# uC.net
KiCad netlist of a schematic drawn in Altium Designer
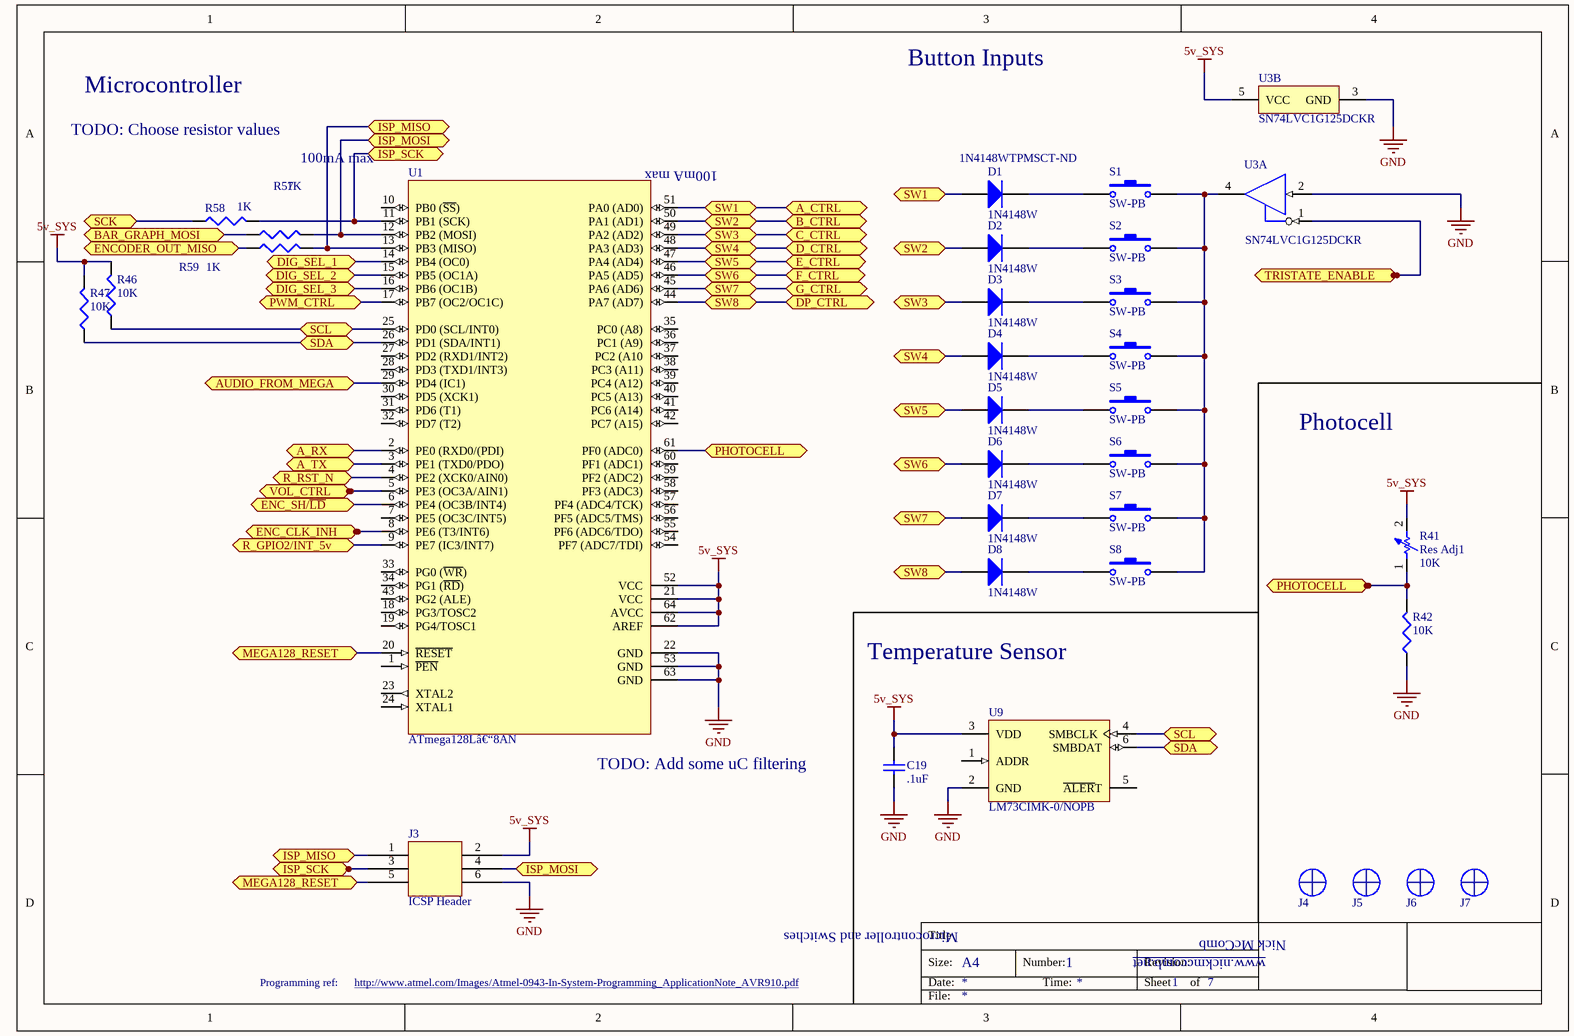
[diagram p0: uC.SchDoc]

(export (version "E")
  (design (tool "Eeschema 10.0.6"))
  (components
    (comp (ref "C19")
      (value ".1uF")
      (footprint "C0805")
      (description "Capacitor")
      (fields (field (name "Comment") "0805 style, by default") (field (name "PUBLISHER") "Altium Limited"))
      (libsource (lib "mega48") (part "Cap"))
    )
    (comp (ref "D1")
      (value "1N4148W")
      (footprint "JSCJ-SOD-123-2_V")
      (description "Fast Switching Diode, 75 V, 150 mA, 2-Pin 2.7 x 1.6 x 1.25 mm SMD, Tape and Reel")
      (fields
        (field (name "MANUFACTURER") "Changjiang Electronics")
        (field (name "SUPPLIER PART NUMBER 1") "1N4148WTPMSCT-ND")
        (field (name "MANUFACTURER PART NUMBER") "1N4148W-TP")
      )
      (libsource (lib "Altium Content Vault") (part "JSCJ-A1K2-2"))
    )
    (comp (ref "D2")
      (value "1N4148W")
      (footprint "JSCJ-SOD-123-2_V")
      (description "Fast Switching Diode, 75 V, 150 mA, 2-Pin 2.7 x 1.6 x 1.25 mm SMD, Tape and Reel")
      (fields
        (field (name "MANUFACTURER") "Changjiang Electronics")
        (field (name "MANUFACTURER PART NUMBER") "1N4148W-TP")
      )
      (libsource (lib "Altium Content Vault") (part "CMP-0914-00001-1"))
    )
    (comp (ref "D3")
      (value "1N4148W")
      (footprint "JSCJ-SOD-123-2_V")
      (description "Fast Switching Diode, 75 V, 150 mA, 2-Pin 2.7 x 1.6 x 1.25 mm SMD, Tape and Reel")
      (fields
        (field (name "MANUFACTURER") "Changjiang Electronics")
        (field (name "MANUFACTURER PART NUMBER") "1N4148W-TP")
      )
      (libsource (lib "Altium Content Vault") (part "CMP-0914-00001-1"))
    )
    (comp (ref "D4")
      (value "1N4148W")
      (footprint "JSCJ-SOD-123-2_V")
      (description "Fast Switching Diode, 75 V, 150 mA, 2-Pin 2.7 x 1.6 x 1.25 mm SMD, Tape and Reel")
      (fields
        (field (name "MANUFACTURER") "Changjiang Electronics")
        (field (name "MANUFACTURER PART NUMBER") "1N4148W-TP")
      )
      (libsource (lib "Altium Content Vault") (part "CMP-0914-00001-1"))
    )
    (comp (ref "D5")
      (value "1N4148W")
      (footprint "JSCJ-SOD-123-2_V")
      (description "Fast Switching Diode, 75 V, 150 mA, 2-Pin 2.7 x 1.6 x 1.25 mm SMD, Tape and Reel")
      (fields
        (field (name "MANUFACTURER") "Changjiang Electronics")
        (field (name "MANUFACTURER PART NUMBER") "1N4148W-TP")
      )
      (libsource (lib "Altium Content Vault") (part "CMP-0914-00001-1"))
    )
    (comp (ref "D6")
      (value "1N4148W")
      (footprint "JSCJ-SOD-123-2_V")
      (description "Fast Switching Diode, 75 V, 150 mA, 2-Pin 2.7 x 1.6 x 1.25 mm SMD, Tape and Reel")
      (fields
        (field (name "MANUFACTURER") "Changjiang Electronics")
        (field (name "MANUFACTURER PART NUMBER") "1N4148W-TP")
      )
      (libsource (lib "Altium Content Vault") (part "CMP-0914-00001-1"))
    )
    (comp (ref "D7")
      (value "1N4148W")
      (footprint "JSCJ-SOD-123-2_V")
      (description "Fast Switching Diode, 75 V, 150 mA, 2-Pin 2.7 x 1.6 x 1.25 mm SMD, Tape and Reel")
      (fields
        (field (name "MANUFACTURER") "Changjiang Electronics")
        (field (name "MANUFACTURER PART NUMBER") "1N4148W-TP")
      )
      (libsource (lib "Altium Content Vault") (part "CMP-0914-00001-1"))
    )
    (comp (ref "D8")
      (value "1N4148W")
      (footprint "JSCJ-SOD-123-2_V")
      (description "Fast Switching Diode, 75 V, 150 mA, 2-Pin 2.7 x 1.6 x 1.25 mm SMD, Tape and Reel")
      (fields
        (field (name "MANUFACTURER") "Changjiang Electronics")
        (field (name "MANUFACTURER PART NUMBER") "1N4148W-TP")
      )
      (libsource (lib "Altium Content Vault") (part "CMP-0914-00001-1"))
    )
    (comp (ref "J3")
      (value "ICSP Header")
      (footprint "ICSP Header")
      (libsource (lib "lab2") (part "ICSP Header"))
    )
    (comp (ref "J4")
      (value "MountingHoles")
      (footprint "Mounting Hole - Single")
      (libsource (lib "lab2") (part "MountingHoles"))
    )
    (comp (ref "J5")
      (value "MountingHoles")
      (footprint "Mounting Hole - Single")
      (libsource (lib "lab2") (part "MountingHoles"))
    )
    (comp (ref "J6")
      (value "MountingHoles")
      (footprint "Mounting Hole - Single")
      (libsource (lib "lab2") (part "MountingHoles"))
    )
    (comp (ref "J7")
      (value "MountingHoles")
      (footprint "Mounting Hole - Single")
      (libsource (lib "lab2") (part "MountingHoles"))
    )
    (comp (ref "R41")
      (value "Res Adj1")
      (footprint "PHOTOCELL")
      (description "Variable Resistor")
      (fields (field (name "ALTIUM_VALUE") "10K"))
      (libsource (lib "lab2") (part "Res Adj1"))
    )
    (comp (ref "R42")
      (value "10K")
      (footprint "J1-0603")
      (description "Resistor")
      (fields (field (name "PUBLISHER") "Altium Limited"))
      (libsource (lib "lab2") (part "Res3"))
    )
    (comp (ref "R46")
      (value "10K")
      (footprint "J1-0603")
      (description "Resistor")
      (fields (field (name "PUBLISHER") "Altium Limited"))
      (libsource (lib "lab2") (part "Res3"))
    )
    (comp (ref "R47")
      (value "10K")
      (footprint "J1-0603")
      (description "Resistor")
      (fields (field (name "PUBLISHER") "Altium Limited"))
      (libsource (lib "lab2") (part "Res3"))
    )
    (comp (ref "R57")
      (value "1K")
      (footprint "J1-0603")
      (description "Resistor")
      (fields (field (name "PUBLISHER") "Altium Limited"))
      (libsource (lib "lab2") (part "Res3"))
    )
    (comp (ref "R58")
      (value "1K")
      (footprint "J1-0603")
      (description "Resistor")
      (fields (field (name "PUBLISHER") "Altium Limited"))
      (libsource (lib "lab2") (part "Res3"))
    )
    (comp (ref "R59")
      (value "1K")
      (footprint "J1-0603")
      (description "Resistor")
      (fields (field (name "PUBLISHER") "Altium Limited"))
      (libsource (lib "lab2") (part "Res3"))
    )
    (comp (ref "S1")
      (value "SW-PB")
      (footprint "SW-PB")
      (description "Switch")
      (libsource (lib "lab2") (part "SW-PB"))
    )
    (comp (ref "S2")
      (value "SW-PB")
      (footprint "SW-PB")
      (description "Switch")
      (libsource (lib "lab2") (part "SW-PB"))
    )
    (comp (ref "S3")
      (value "SW-PB")
      (footprint "SW-PB")
      (description "Switch")
      (libsource (lib "lab2") (part "SW-PB"))
    )
    (comp (ref "S4")
      (value "SW-PB")
      (footprint "SW-PB")
      (description "Switch")
      (libsource (lib "lab2") (part "SW-PB"))
    )
    (comp (ref "S5")
      (value "SW-PB")
      (footprint "SW-PB")
      (description "Switch")
      (libsource (lib "lab2") (part "SW-PB"))
    )
    (comp (ref "S6")
      (value "SW-PB")
      (footprint "SW-PB")
      (description "Switch")
      (libsource (lib "lab2") (part "SW-PB"))
    )
    (comp (ref "S7")
      (value "SW-PB")
      (footprint "SW-PB")
      (description "Switch")
      (libsource (lib "lab2") (part "SW-PB"))
    )
    (comp (ref "S8")
      (value "SW-PB")
      (footprint "SW-PB")
      (description "Switch")
      (libsource (lib "lab2") (part "SW-PB"))
    )
    (comp (ref "U1")
      (value "ATmega128Lâ€“8AN")
      (footprint "64A_M")
      (libsource (lib "Altium Content Vault") (part "MC-8B-AT64-SQ64"))
    )
    (comp (ref "U3")
      (value "SN74LVC1G125DCKR")
      (footprint "DCK0005A_M")
      (description "Single Bus Buffer Gate With 3-State Outputs, DCK0005A, LARGE T&R")
      (fields
        (field (name "GENERIC PART NUMBER") "SN74LVC1G125")
        (field (name "MANUFACTURER") "Texas Instruments")
      )
      (libsource (lib "Altium Content Vault") (part "TI-SN74AXXXX1X125-5"))
    )
    (comp (ref "U9")
      (value "LM73CIMK-0/NOPB")
      (footprint "DDC0006A_M")
      (description "2.7V, 11- to 14- Bit Digital Temperature Sensor with 2-Wire Interface, 6-pin Tiny SOT23, Pb-Free")
      (fields (field (name "MANUFACTURER") "Texas Instruments"))
      (libsource (lib "Altium Content Vault") (part "SEN-TEMP-LM73CIMK-6"))
    )
  )
  (nets
    (net (code "1") (name "/AUDIO_FROM_MEGA") (class "Default")
      (node (ref "U1") (pin "29") (pinfunction "PD4_(IC1)_29") (pintype "bidirectional"))
    )
    (net (code "2") (name "/A_CTRL") (class "Default")
      (node (ref "D1") (pin "1") (pinfunction "+_1") (pintype "passive"))
      (node (ref "U1") (pin "51") (pinfunction "PA0_(AD0)_51") (pintype "bidirectional"))
    )
    (net (code "3") (name "/A_RX") (class "Default")
      (node (ref "U1") (pin "2") (pinfunction "PE0_(RXD0/(PDI)_2") (pintype "bidirectional"))
    )
    (net (code "4") (name "/A_TX") (class "Default")
      (node (ref "U1") (pin "3") (pinfunction "PE1_(TXD0/PDO)_3") (pintype "bidirectional"))
    )
    (net (code "5") (name "/BAR_GRAPH_MOSI") (class "Default")
      (node (ref "R57") (pin "1") (pinfunction "1_1") (pintype "passive"))
    )
    (net (code "6") (name "/B_CTRL") (class "Default")
      (node (ref "D2") (pin "1") (pinfunction "+_1") (pintype "passive"))
      (node (ref "U1") (pin "50") (pinfunction "PA1_(AD1)_50") (pintype "bidirectional"))
    )
    (net (code "7") (name "/C_CTRL") (class "Default")
      (node (ref "D3") (pin "1") (pinfunction "+_1") (pintype "passive"))
      (node (ref "U1") (pin "49") (pinfunction "PA2_(AD2)_49") (pintype "bidirectional"))
    )
    (net (code "8") (name "/DIG_SEL_1") (class "Default")
      (node (ref "U1") (pin "14") (pinfunction "PB4_(OC0)_14") (pintype "bidirectional"))
    )
    (net (code "9") (name "/DIG_SEL_2") (class "Default")
      (node (ref "U1") (pin "15") (pinfunction "PB5_(OC1A)_15") (pintype "bidirectional"))
    )
    (net (code "10") (name "/DIG_SEL_3") (class "Default")
      (node (ref "U1") (pin "16") (pinfunction "PB6_(OC1B)_16") (pintype "bidirectional"))
    )
    (net (code "11") (name "/DP_CTRL") (class "Default")
      (node (ref "D8") (pin "1") (pinfunction "+_1") (pintype "passive"))
      (node (ref "U1") (pin "44") (pinfunction "PA7_(AD7)_44") (pintype "bidirectional"))
    )
    (net (code "12") (name "/D_CTRL") (class "Default")
      (node (ref "D4") (pin "1") (pinfunction "+_1") (pintype "passive"))
      (node (ref "U1") (pin "48") (pinfunction "PA3_(AD3)_48") (pintype "bidirectional"))
    )
    (net (code "13") (name "/ENCODER_OUT_MISO") (class "Default")
      (node (ref "R59") (pin "1") (pinfunction "1_1") (pintype "passive"))
    )
    (net (code "14") (name "/ENC_CLK_INH") (class "Default")
      (node (ref "U1") (pin "8") (pinfunction "PE6_(T3/INT6)_8") (pintype "bidirectional"))
    )
    (net (code "15") (name "/ENC_SH{slash}~{LD}") (class "Default")
      (node (ref "U1") (pin "6") (pinfunction "PE4_(OC3B/INT4)_6") (pintype "bidirectional"))
    )
    (net (code "16") (name "/E_CTRL") (class "Default")
      (node (ref "D5") (pin "1") (pinfunction "+_1") (pintype "passive"))
      (node (ref "U1") (pin "47") (pinfunction "PA4_(AD4)_47") (pintype "bidirectional"))
    )
    (net (code "17") (name "/F_CTRL") (class "Default")
      (node (ref "D6") (pin "1") (pinfunction "+_1") (pintype "passive"))
      (node (ref "U1") (pin "46") (pinfunction "PA5_(AD5)_46") (pintype "bidirectional"))
    )
    (net (code "18") (name "/G_CTRL") (class "Default")
      (node (ref "D7") (pin "1") (pinfunction "+_1") (pintype "passive"))
      (node (ref "U1") (pin "45") (pinfunction "PA6_(AD6)_45") (pintype "bidirectional"))
    )
    (net (code "19") (name "/ISP_MISO") (class "Default")
      (node (ref "J3") (pin "1") (pintype "passive"))
      (node (ref "R59") (pin "2") (pinfunction "2_2") (pintype "passive"))
      (node (ref "U1") (pin "13") (pinfunction "PB3_(MISO)_13") (pintype "bidirectional"))
    )
    (net (code "20") (name "/ISP_MOSI") (class "Default")
      (node (ref "J3") (pin "4") (pintype "passive"))
      (node (ref "R57") (pin "2") (pinfunction "2_2") (pintype "passive"))
      (node (ref "U1") (pin "12") (pinfunction "PB2_(MOSI)_12") (pintype "bidirectional"))
    )
    (net (code "21") (name "/ISP_SCK") (class "Default")
      (node (ref "J3") (pin "3") (pintype "passive"))
      (node (ref "R58") (pin "2") (pinfunction "2_2") (pintype "passive"))
      (node (ref "U1") (pin "11") (pinfunction "PB1_(SCK)_11") (pintype "bidirectional"))
    )
    (net (code "22") (name "/MEGA128_RESET") (class "Default")
      (node (ref "J3") (pin "5") (pintype "passive"))
      (node (ref "U1") (pin "20") (pinfunction "~{RESET}_20") (pintype "input"))
    )
    (net (code "23") (name "/PHOTOCELL") (class "Default")
      (node (ref "R41") (pin "1") (pinfunction "1_1") (pintype "passive"))
      (node (ref "R42") (pin "2") (pinfunction "2_2") (pintype "passive"))
      (node (ref "U1") (pin "61") (pinfunction "PF0_(ADC0)_61") (pintype "bidirectional"))
    )
    (net (code "24") (name "/PWM_CTRL") (class "Default")
      (node (ref "U1") (pin "17") (pinfunction "PB7_(OC2/OC1C)_17") (pintype "bidirectional"))
    )
    (net (code "25") (name "/R_GPIO2{slash}INT_5v") (class "Default")
      (node (ref "U1") (pin "9") (pinfunction "PE7_(IC3/INT7)_9") (pintype "bidirectional"))
    )
    (net (code "26") (name "/R_RST_N") (class "Default")
      (node (ref "U1") (pin "4") (pinfunction "PE2_(XCK0/AIN0)_4") (pintype "bidirectional"))
    )
    (net (code "27") (name "/SCK") (class "Default")
      (node (ref "R58") (pin "1") (pinfunction "1_1") (pintype "passive"))
    )
    (net (code "28") (name "/SCL") (class "Default")
      (node (ref "R46") (pin "1") (pinfunction "1_1") (pintype "passive"))
      (node (ref "U1") (pin "25") (pinfunction "PD0_(SCL/INT0)_25") (pintype "bidirectional"))
      (node (ref "U9") (pin "4") (pinfunction "SMBCLK_4") (pintype "input"))
    )
    (net (code "29") (name "/SDA") (class "Default")
      (node (ref "R47") (pin "1") (pinfunction "1_1") (pintype "passive"))
      (node (ref "U1") (pin "26") (pinfunction "PD1_(SDA/INT1)_26") (pintype "bidirectional"))
      (node (ref "U9") (pin "6") (pinfunction "SMBDAT_6") (pintype "bidirectional"))
    )
    (net (code "30") (name "/TRISTATE_ENABLE") (class "Default")
      (node (ref "U3") (pin "1") (pinfunction "~{OE}_1") (pintype "input"))
    )
    (net (code "31") (name "/VOL_CTRL") (class "Default")
      (node (ref "U1") (pin "5") (pinfunction "PE3_(OC3A/AIN1)_5") (pintype "bidirectional"))
    )
    (net (code "32") (name "5v_SYS") (class "Default")
      (node (ref "C19") (pin "2") (pinfunction "2_2") (pintype "passive"))
      (node (ref "J3") (pin "2") (pintype "passive"))
      (node (ref "R41") (pin "2") (pinfunction "2_2") (pintype "passive"))
      (node (ref "R46") (pin "2") (pinfunction "2_2") (pintype "passive"))
      (node (ref "R47") (pin "2") (pinfunction "2_2") (pintype "passive"))
      (node (ref "U1") (pin "21") (pinfunction "VCC_21") (pintype "power_in"))
      (node (ref "U1") (pin "52") (pinfunction "VCC_52") (pintype "power_in"))
      (node (ref "U1") (pin "62") (pinfunction "AREF_62") (pintype "passive"))
      (node (ref "U1") (pin "64") (pinfunction "AVCC_64") (pintype "power_in"))
      (node (ref "U3") (pin "5") (pinfunction "VCC_5") (pintype "power_in"))
      (node (ref "U9") (pin "3") (pinfunction "VDD_3") (pintype "power_in"))
    )
    (net (code "33") (name "GND") (class "Default")
      (node (ref "C19") (pin "1") (pinfunction "1_1") (pintype "passive"))
      (node (ref "J3") (pin "6") (pintype "passive"))
      (node (ref "R42") (pin "1") (pinfunction "1_1") (pintype "passive"))
      (node (ref "U1") (pin "22") (pinfunction "GND_22") (pintype "power_in"))
      (node (ref "U1") (pin "53") (pinfunction "GND_53") (pintype "power_in"))
      (node (ref "U1") (pin "63") (pinfunction "GND_63") (pintype "power_in"))
      (node (ref "U3") (pin "2") (pinfunction "A_2") (pintype "input"))
      (node (ref "U3") (pin "3") (pinfunction "GND_3") (pintype "power_in"))
      (node (ref "U9") (pin "2") (pinfunction "GND_2") (pintype "power_in"))
    )
    (net (code "34") (name "Net-(D1--)") (class "Default")
      (node (ref "D1") (pin "2") (pinfunction "-_2") (pintype "passive"))
      (node (ref "S1") (pin "1") (pinfunction "1_1") (pintype "passive"))
    )
    (net (code "35") (name "Net-(D2--)") (class "Default")
      (node (ref "D2") (pin "2") (pinfunction "-_2") (pintype "passive"))
      (node (ref "S2") (pin "1") (pinfunction "1_1") (pintype "passive"))
    )
    (net (code "36") (name "Net-(D3--)") (class "Default")
      (node (ref "D3") (pin "2") (pinfunction "-_2") (pintype "passive"))
      (node (ref "S3") (pin "1") (pinfunction "1_1") (pintype "passive"))
    )
    (net (code "37") (name "Net-(D4--)") (class "Default")
      (node (ref "D4") (pin "2") (pinfunction "-_2") (pintype "passive"))
      (node (ref "S4") (pin "1") (pinfunction "1_1") (pintype "passive"))
    )
    (net (code "38") (name "Net-(D5--)") (class "Default")
      (node (ref "D5") (pin "2") (pinfunction "-_2") (pintype "passive"))
      (node (ref "S5") (pin "1") (pinfunction "1_1") (pintype "passive"))
    )
    (net (code "39") (name "Net-(D6--)") (class "Default")
      (node (ref "D6") (pin "2") (pinfunction "-_2") (pintype "passive"))
      (node (ref "S6") (pin "1") (pinfunction "1_1") (pintype "passive"))
    )
    (net (code "40") (name "Net-(D7--)") (class "Default")
      (node (ref "D7") (pin "2") (pinfunction "-_2") (pintype "passive"))
      (node (ref "S7") (pin "1") (pinfunction "1_1") (pintype "passive"))
    )
    (net (code "41") (name "Net-(D8--)") (class "Default")
      (node (ref "D8") (pin "2") (pinfunction "-_2") (pintype "passive"))
      (node (ref "S8") (pin "1") (pinfunction "1_1") (pintype "passive"))
    )
    (net (code "42") (name "Net-(U3A-Y)") (class "Default")
      (node (ref "S1") (pin "2") (pinfunction "2_2") (pintype "passive"))
      (node (ref "S2") (pin "2") (pinfunction "2_2") (pintype "passive"))
      (node (ref "S3") (pin "2") (pinfunction "2_2") (pintype "passive"))
      (node (ref "S4") (pin "2") (pinfunction "2_2") (pintype "passive"))
      (node (ref "S5") (pin "2") (pinfunction "2_2") (pintype "passive"))
      (node (ref "S6") (pin "2") (pinfunction "2_2") (pintype "passive"))
      (node (ref "S7") (pin "2") (pinfunction "2_2") (pintype "passive"))
      (node (ref "S8") (pin "2") (pinfunction "2_2") (pintype "passive"))
      (node (ref "U3") (pin "4") (pinfunction "Y_4") (pintype "tri_state"))
    )
    (net (code "43") (name "unconnected-(U1-PB0_(~{SS})-Pad10)") (class "Default")
      (node (ref "U1") (pin "10") (pinfunction "PB0_(~{SS})_10") (pintype "bidirectional"))
    )
    (net (code "44") (name "unconnected-(U1-PC0_(A8)-Pad35)") (class "Default")
      (node (ref "U1") (pin "35") (pinfunction "PC0_(A8)_35") (pintype "bidirectional"))
    )
    (net (code "45") (name "unconnected-(U1-PC1_(A9)-Pad36)") (class "Default")
      (node (ref "U1") (pin "36") (pinfunction "PC1_(A9)_36") (pintype "bidirectional"))
    )
    (net (code "46") (name "unconnected-(U1-PC2_(A10-Pad37)") (class "Default")
      (node (ref "U1") (pin "37") (pinfunction "PC2_(A10_37") (pintype "bidirectional"))
    )
    (net (code "47") (name "unconnected-(U1-PC3_(A11)-Pad38)") (class "Default")
      (node (ref "U1") (pin "38") (pinfunction "PC3_(A11)_38") (pintype "bidirectional"))
    )
    (net (code "48") (name "unconnected-(U1-PC4_(A12)-Pad39)") (class "Default")
      (node (ref "U1") (pin "39") (pinfunction "PC4_(A12)_39") (pintype "bidirectional"))
    )
    (net (code "49") (name "unconnected-(U1-PC5_(A13)-Pad40)") (class "Default")
      (node (ref "U1") (pin "40") (pinfunction "PC5_(A13)_40") (pintype "bidirectional"))
    )
    (net (code "50") (name "unconnected-(U1-PC6_(A14)-Pad41)") (class "Default")
      (node (ref "U1") (pin "41") (pinfunction "PC6_(A14)_41") (pintype "bidirectional"))
    )
    (net (code "51") (name "unconnected-(U1-PC7_(A15)-Pad42)") (class "Default")
      (node (ref "U1") (pin "42") (pinfunction "PC7_(A15)_42") (pintype "bidirectional"))
    )
    (net (code "52") (name "unconnected-(U1-PD2_(RXD1{slash}INT2)-Pad27)") (class "Default")
      (node (ref "U1") (pin "27") (pinfunction "PD2_(RXD1/INT2)_27") (pintype "bidirectional"))
    )
    (net (code "53") (name "unconnected-(U1-PD3_(TXD1{slash}INT3)-Pad28)") (class "Default")
      (node (ref "U1") (pin "28") (pinfunction "PD3_(TXD1/INT3)_28") (pintype "bidirectional"))
    )
    (net (code "54") (name "unconnected-(U1-PD5_(XCK1)-Pad30)") (class "Default")
      (node (ref "U1") (pin "30") (pinfunction "PD5_(XCK1)_30") (pintype "bidirectional"))
    )
    (net (code "55") (name "unconnected-(U1-PD6_(T1)-Pad31)") (class "Default")
      (node (ref "U1") (pin "31") (pinfunction "PD6_(T1)_31") (pintype "bidirectional"))
    )
    (net (code "56") (name "unconnected-(U1-PD7_(T2)-Pad32)") (class "Default")
      (node (ref "U1") (pin "32") (pinfunction "PD7_(T2)_32") (pintype "bidirectional"))
    )
    (net (code "57") (name "unconnected-(U1-PE5_(OC3C{slash}INT5)-Pad7)") (class "Default")
      (node (ref "U1") (pin "7") (pinfunction "PE5_(OC3C/INT5)_7") (pintype "bidirectional"))
    )
    (net (code "58") (name "unconnected-(U1-PF1_(ADC1)-Pad60)") (class "Default")
      (node (ref "U1") (pin "60") (pinfunction "PF1_(ADC1)_60") (pintype "bidirectional"))
    )
    (net (code "59") (name "unconnected-(U1-PF2_(ADC2)-Pad59)") (class "Default")
      (node (ref "U1") (pin "59") (pinfunction "PF2_(ADC2)_59") (pintype "bidirectional"))
    )
    (net (code "60") (name "unconnected-(U1-PF3_(ADC3)-Pad58)") (class "Default")
      (node (ref "U1") (pin "58") (pinfunction "PF3_(ADC3)_58") (pintype "bidirectional"))
    )
    (net (code "61") (name "unconnected-(U1-PF4_(ADC4{slash}TCK)-Pad57)") (class "Default")
      (node (ref "U1") (pin "57") (pinfunction "PF4_(ADC4/TCK)_57") (pintype "bidirectional"))
    )
    (net (code "62") (name "unconnected-(U1-PF5_(ADC5{slash}TMS)-Pad56)") (class "Default")
      (node (ref "U1") (pin "56") (pinfunction "PF5_(ADC5/TMS)_56") (pintype "bidirectional"))
    )
    (net (code "63") (name "unconnected-(U1-PF6_(ADC6{slash}TDO)-Pad55)") (class "Default")
      (node (ref "U1") (pin "55") (pinfunction "PF6_(ADC6/TDO)_55") (pintype "bidirectional"))
    )
    (net (code "64") (name "unconnected-(U1-PF7_(ADC7{slash}TDI)-Pad54)") (class "Default")
      (node (ref "U1") (pin "54") (pinfunction "PF7_(ADC7/TDI)_54") (pintype "bidirectional"))
    )
    (net (code "65") (name "unconnected-(U1-PG0_(~{WR})-Pad33)") (class "Default")
      (node (ref "U1") (pin "33") (pinfunction "PG0_(~{WR})_33") (pintype "bidirectional"))
    )
    (net (code "66") (name "unconnected-(U1-PG1_(~{RD})-Pad34)") (class "Default")
      (node (ref "U1") (pin "34") (pinfunction "PG1_(~{RD})_34") (pintype "bidirectional"))
    )
    (net (code "67") (name "unconnected-(U1-PG2_(ALE)-Pad43)") (class "Default")
      (node (ref "U1") (pin "43") (pinfunction "PG2_(ALE)_43") (pintype "bidirectional"))
    )
    (net (code "68") (name "unconnected-(U1-PG3{slash}TOSC2-Pad18)") (class "Default")
      (node (ref "U1") (pin "18") (pinfunction "PG3/TOSC2_18") (pintype "bidirectional"))
    )
    (net (code "69") (name "unconnected-(U1-PG4{slash}TOSC1-Pad19)") (class "Default")
      (node (ref "U1") (pin "19") (pinfunction "PG4/TOSC1_19") (pintype "bidirectional"))
    )
    (net (code "70") (name "unconnected-(U1-XTAL1-Pad24)") (class "Default")
      (node (ref "U1") (pin "24") (pinfunction "XTAL1_24") (pintype "input"))
    )
    (net (code "71") (name "unconnected-(U1-XTAL2-Pad23)") (class "Default")
      (node (ref "U1") (pin "23") (pinfunction "XTAL2_23") (pintype "output"))
    )
    (net (code "72") (name "unconnected-(U1-~{PEN}-Pad1)") (class "Default")
      (node (ref "U1") (pin "1") (pinfunction "~{PEN}_1") (pintype "input"))
    )
    (net (code "73") (name "unconnected-(U9-ADDR-Pad1)") (class "Default")
      (node (ref "U9") (pin "1") (pinfunction "ADDR_1") (pintype "input"))
    )
    (net (code "74") (name "unconnected-(U9-~{ALER}T-Pad5)") (class "Default")
      (node (ref "U9") (pin "5") (pinfunction "~{ALER}T_5") (pintype "open_collector"))
    )
  )
)
